# ST_LINK_V3E.net
KiCad netlist of a schematic drawn in Altium Designer
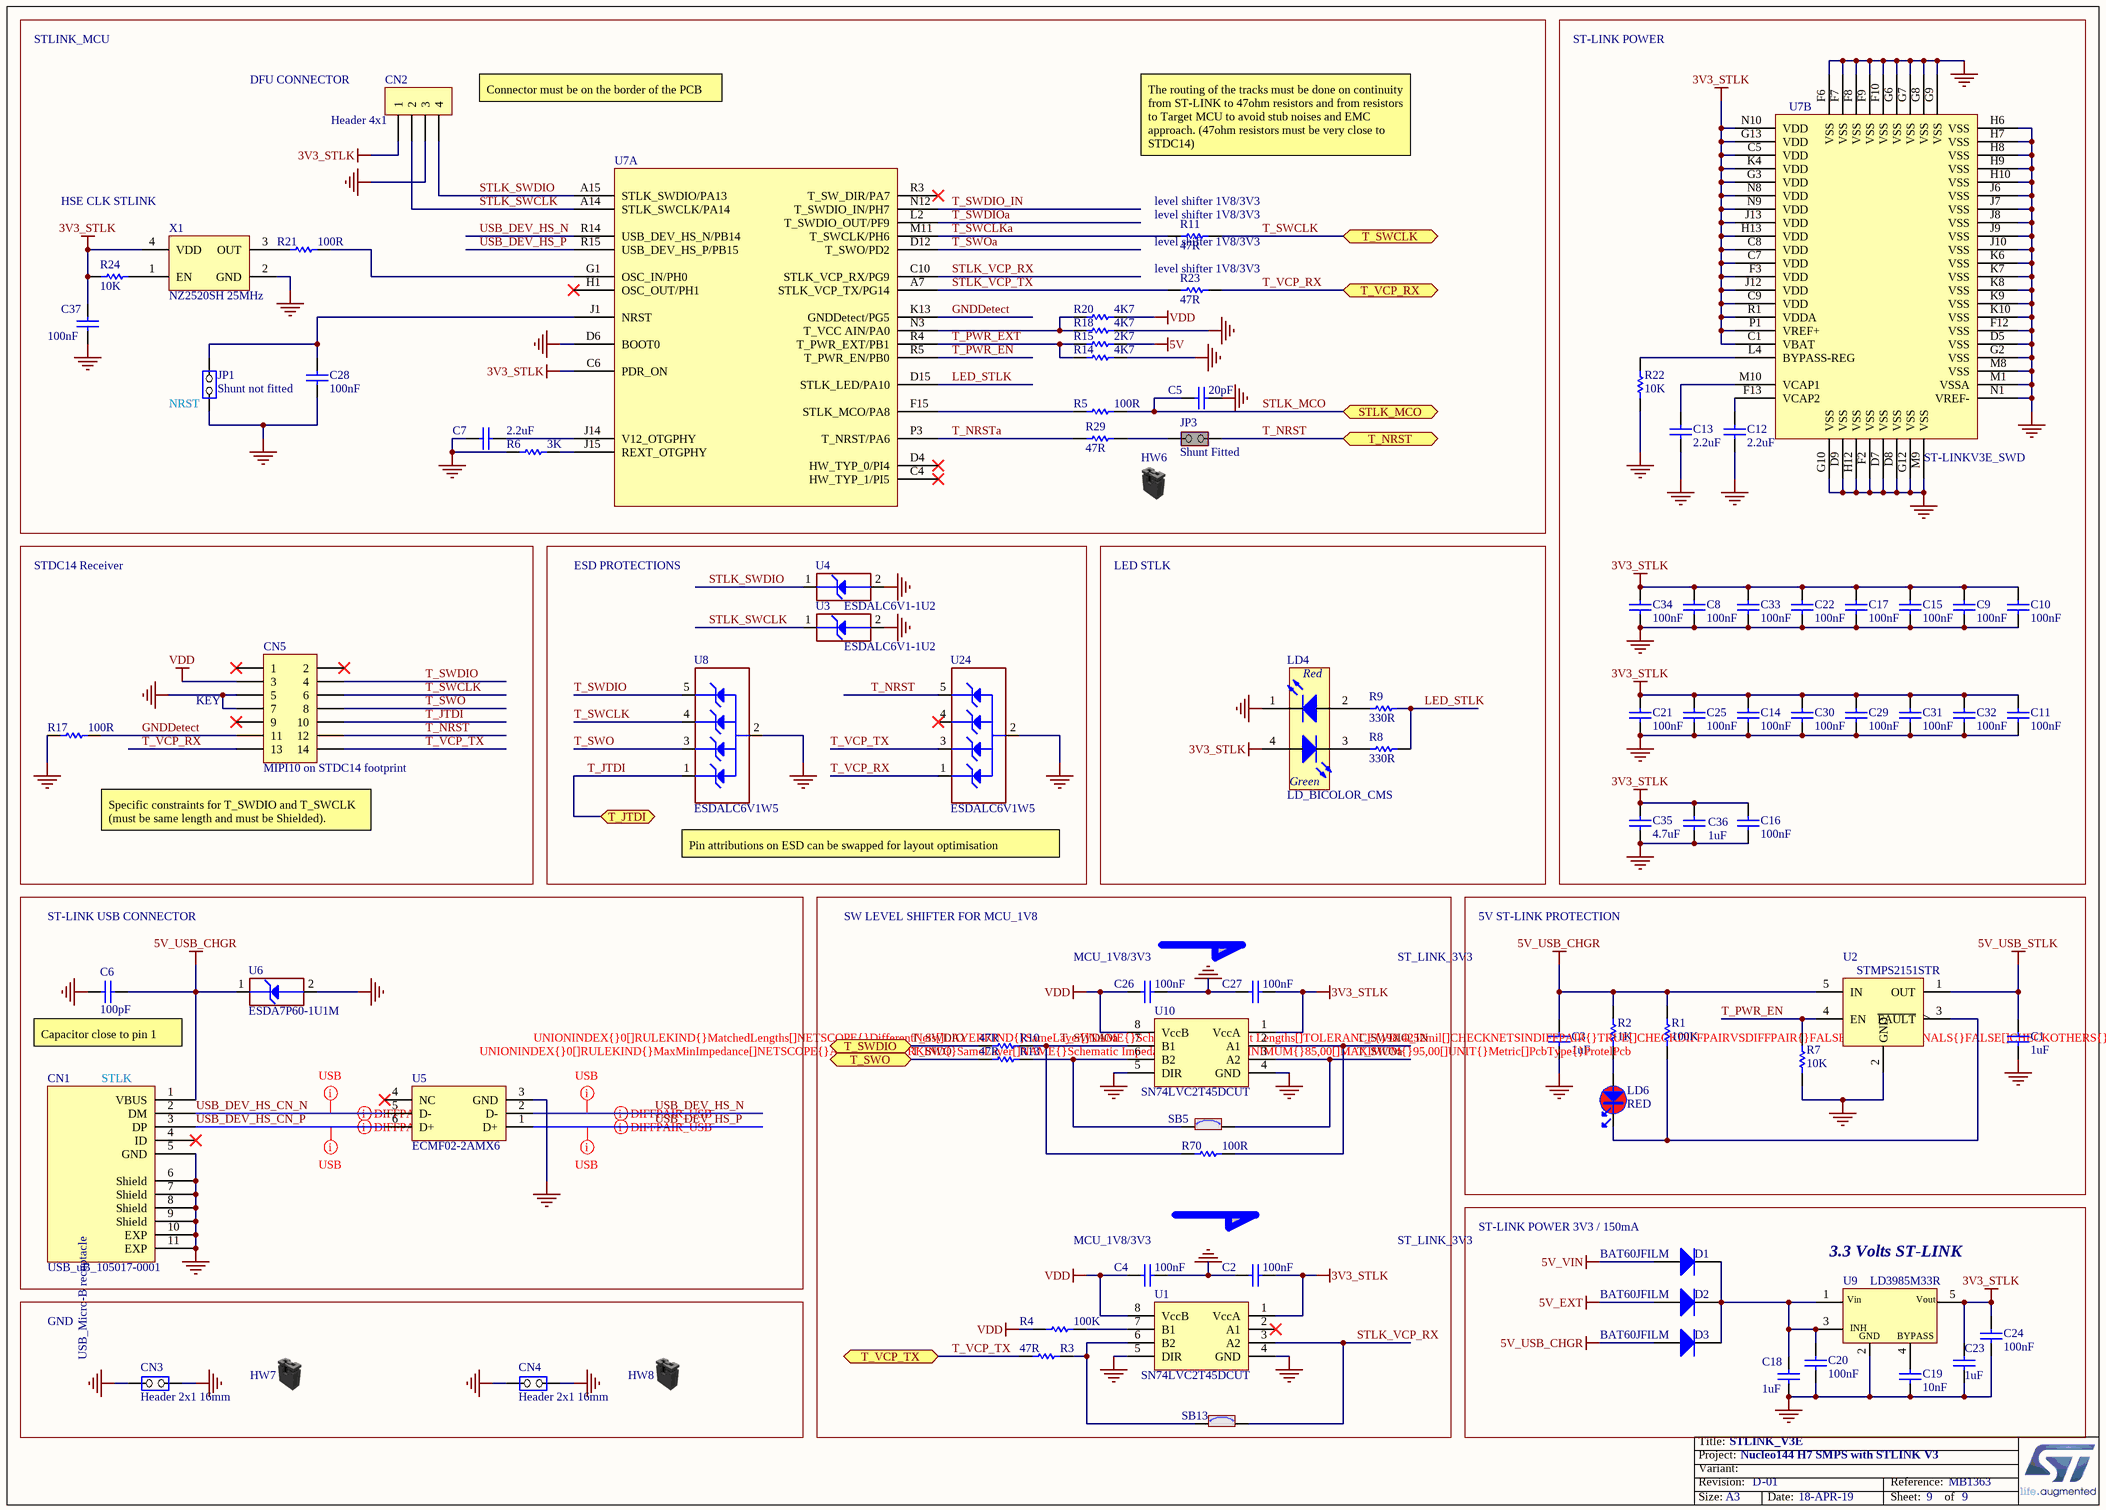
[diagram p0: ST_LINK_V3E.SchDoc]

(export (version "E")
  (design (tool "Eeschema 10.0.6"))
  (components
    (comp (ref "C1")
      (value "1uF")
      (footprint "C0603")
      (description "Capacitor, MLCC, 1uF, 6V3, X5R, 10%, 0603, T=0,8mm")
      (fields
        (field (name "INTERNAL_PART_NUMBER") "MCD-00238")
        (field (name "MANUFACTURER_PART_NUMBER") "CC0603KRX5R5BB105")
        (field (name "PROVIDED_BY") "SUBCO")
      )
      (libsource (lib "MCD_PARTS_database") (part "Capacitor"))
    )
    (comp (ref "C2")
      (value "100nF")
      (footprint "C0603")
      (description "Capacitor, MLCC, 100nF, 16V, X7R, 10%, 0603, T=0,8mm")
      (fields
        (field (name "INTERNAL_PART_NUMBER") "MCD-00211")
        (field (name "MANUFACTURER_PART_NUMBER") "CC0603KRX7R7BB104")
        (field (name "PROVIDED_BY") "SUBCO")
      )
      (libsource (lib "MCD_PARTS_database") (part "Capacitor"))
    )
    (comp (ref "C3")
      (value "1uF")
      (footprint "C0603")
      (description "Capacitor, MLCC, 1uF, 6V3, X5R, 10%, 0603, T=0,8mm")
      (fields
        (field (name "INTERNAL_PART_NUMBER") "MCD-00238")
        (field (name "MANUFACTURER_PART_NUMBER") "CC0603KRX5R5BB105")
        (field (name "PROVIDED_BY") "SUBCO")
      )
      (libsource (lib "MCD_PARTS_database") (part "Capacitor"))
    )
    (comp (ref "C4")
      (value "100nF")
      (footprint "C0603")
      (description "Capacitor, MLCC, 100nF, 16V, X7R, 10%, 0603, T=0,8mm")
      (fields
        (field (name "INTERNAL_PART_NUMBER") "MCD-00211")
        (field (name "MANUFACTURER_PART_NUMBER") "CC0603KRX7R7BB104")
        (field (name "PROVIDED_BY") "SUBCO")
      )
      (libsource (lib "MCD_PARTS_database") (part "Capacitor"))
    )
    (comp (ref "C5")
      (value "20pF")
      (footprint "C0402")
      (description "Capacitor, MLCC, 20pF, 50V, NPO, 5%, 0402, T=0,5mm")
      (fields
        (field (name "INTERNAL_PART_NUMBER") "MCD-00016")
        (field (name "MANUFACTURER_PART_NUMBER") "CC0402JRNPO9BN200")
        (field (name "PROVIDED_BY") "SUBCO")
      )
      (libsource (lib "MCD_PARTS_database") (part "Capacitor"))
    )
    (comp (ref "C6")
      (value "100pF")
      (footprint "C0402")
      (description "Capacitor, MLCC, 100pF, 50V, NPO, 5%, 0402, T=0,5mm")
      (fields
        (field (name "INTERNAL_PART_NUMBER") "MCD-00205")
        (field (name "MANUFACTURER_PART_NUMBER") "CC0402JRNPO9BN101")
        (field (name "PROVIDED_BY") "SUBCO")
      )
      (libsource (lib "MCD_PARTS_database") (part "Capacitor"))
    )
    (comp (ref "C7")
      (value "2.2uF")
      (footprint "C0603")
      (description "Capacitor, MLCC, 2.2uF, 10V, X5R, 10%, 0603, T=0,8mm")
      (fields
        (field (name "INTERNAL_PART_NUMBER") "MCD-00012")
        (field (name "MANUFACTURER_PART_NUMBER") "CC0603KRX5R6BB225")
        (field (name "PROVIDED_BY") "SUBCO")
      )
      (libsource (lib "MCD_PARTS_database") (part "Capacitor"))
    )
    (comp (ref "C8")
      (value "100nF")
      (footprint "C0402")
      (description "Capacitor, MLCC, 100nF, 16V, X7R, 10%, 0402, T=0,5mm")
      (fields
        (field (name "INTERNAL_PART_NUMBER") "MCD-00102")
        (field (name "MANUFACTURER_PART_NUMBER") "CC0402KRX7R7BB104")
        (field (name "PROVIDED_BY") "SUBCO")
      )
      (libsource (lib "MCD_PARTS_database") (part "Capacitor"))
    )
    (comp (ref "C9")
      (value "100nF")
      (footprint "C0402")
      (description "Capacitor, MLCC, 100nF, 16V, X7R, 10%, 0402, T=0,5mm")
      (fields
        (field (name "INTERNAL_PART_NUMBER") "MCD-00102")
        (field (name "MANUFACTURER_PART_NUMBER") "CC0402KRX7R7BB104")
        (field (name "PROVIDED_BY") "SUBCO")
      )
      (libsource (lib "MCD_PARTS_database") (part "Capacitor"))
    )
    (comp (ref "C10")
      (value "100nF")
      (footprint "C0402")
      (description "Capacitor, MLCC, 100nF, 16V, X7R, 10%, 0402, T=0,5mm")
      (fields
        (field (name "INTERNAL_PART_NUMBER") "MCD-00102")
        (field (name "MANUFACTURER_PART_NUMBER") "CC0402KRX7R7BB104")
        (field (name "PROVIDED_BY") "SUBCO")
      )
      (libsource (lib "MCD_PARTS_database") (part "Capacitor"))
    )
    (comp (ref "C11")
      (value "100nF")
      (footprint "C0402")
      (description "Capacitor, MLCC, 100nF, 16V, X7R, 10%, 0402, T=0,5mm")
      (fields
        (field (name "INTERNAL_PART_NUMBER") "MCD-00102")
        (field (name "MANUFACTURER_PART_NUMBER") "CC0402KRX7R7BB104")
        (field (name "PROVIDED_BY") "SUBCO")
      )
      (libsource (lib "MCD_PARTS_database") (part "Capacitor"))
    )
    (comp (ref "C12")
      (value "2.2uF")
      (footprint "C0603")
      (description "Capacitor, MLCC, 2.2uF, 10V, X5R, 10%, 0603, T=0,8mm")
      (fields
        (field (name "INTERNAL_PART_NUMBER") "MCD-00012")
        (field (name "MANUFACTURER_PART_NUMBER") "CC0603KRX5R6BB225")
        (field (name "PROVIDED_BY") "SUBCO")
      )
      (libsource (lib "MCD_PARTS_database") (part "Capacitor"))
    )
    (comp (ref "C13")
      (value "2.2uF")
      (footprint "C0603")
      (description "Capacitor, MLCC, 2.2uF, 10V, X5R, 10%, 0603, T=0,8mm")
      (fields
        (field (name "INTERNAL_PART_NUMBER") "MCD-00012")
        (field (name "MANUFACTURER_PART_NUMBER") "CC0603KRX5R6BB225")
        (field (name "PROVIDED_BY") "SUBCO")
      )
      (libsource (lib "MCD_PARTS_database") (part "Capacitor"))
    )
    (comp (ref "C14")
      (value "100nF")
      (footprint "C0402")
      (description "Capacitor, MLCC, 100nF, 16V, X7R, 10%, 0402, T=0,5mm")
      (fields
        (field (name "INTERNAL_PART_NUMBER") "MCD-00102")
        (field (name "MANUFACTURER_PART_NUMBER") "CC0402KRX7R7BB104")
        (field (name "PROVIDED_BY") "SUBCO")
      )
      (libsource (lib "MCD_PARTS_database") (part "Capacitor"))
    )
    (comp (ref "C15")
      (value "100nF")
      (footprint "C0402")
      (description "Capacitor, MLCC, 100nF, 16V, X7R, 10%, 0402, T=0,5mm")
      (fields
        (field (name "INTERNAL_PART_NUMBER") "MCD-00102")
        (field (name "MANUFACTURER_PART_NUMBER") "CC0402KRX7R7BB104")
        (field (name "PROVIDED_BY") "SUBCO")
      )
      (libsource (lib "MCD_PARTS_database") (part "Capacitor"))
    )
    (comp (ref "C16")
      (value "100nF")
      (footprint "C0402")
      (description "Capacitor, MLCC, 100nF, 16V, X7R, 10%, 0402, T=0,5mm")
      (fields
        (field (name "INTERNAL_PART_NUMBER") "MCD-00102")
        (field (name "MANUFACTURER_PART_NUMBER") "CC0402KRX7R7BB104")
        (field (name "PROVIDED_BY") "SUBCO")
      )
      (libsource (lib "MCD_PARTS_database") (part "Capacitor"))
    )
    (comp (ref "C17")
      (value "100nF")
      (footprint "C0402")
      (description "Capacitor, MLCC, 100nF, 16V, X7R, 10%, 0402, T=0,5mm")
      (fields
        (field (name "INTERNAL_PART_NUMBER") "MCD-00102")
        (field (name "MANUFACTURER_PART_NUMBER") "CC0402KRX7R7BB104")
        (field (name "PROVIDED_BY") "SUBCO")
      )
      (libsource (lib "MCD_PARTS_database") (part "Capacitor"))
    )
    (comp (ref "C18")
      (value "1uF")
      (footprint "C0603")
      (description "Capacitor, MLCC, 1uF, 6V3, X5R, 10%, 0603, T=0,8mm")
      (fields
        (field (name "INTERNAL_PART_NUMBER") "MCD-00238")
        (field (name "MANUFACTURER_PART_NUMBER") "CC0603KRX5R5BB105")
        (field (name "PROVIDED_BY") "SUBCO")
      )
      (libsource (lib "MCD_PARTS_database") (part "Capacitor"))
    )
    (comp (ref "C19")
      (value "10nF")
      (footprint "C0402")
      (description "Capacitor, MLCC, 10nF, 16V, X7R, 10%, 0402, T=0.5mm")
      (fields
        (field (name "INTERNAL_PART_NUMBER") "MCD-00011")
        (field (name "MANUFACTURER_PART_NUMBER") "CC0402KRX7R7BB103")
        (field (name "PROVIDED_BY") "SUBCO")
      )
      (libsource (lib "MCD_PARTS_database") (part "Capacitor"))
    )
    (comp (ref "C20")
      (value "100nF")
      (footprint "C0402")
      (description "Capacitor, MLCC, 100nF, 16V, X7R, 10%, 0402, T=0,5mm")
      (fields
        (field (name "INTERNAL_PART_NUMBER") "MCD-00102")
        (field (name "MANUFACTURER_PART_NUMBER") "CC0402KRX7R7BB104")
        (field (name "PROVIDED_BY") "SUBCO")
      )
      (libsource (lib "MCD_PARTS_database") (part "Capacitor"))
    )
    (comp (ref "C21")
      (value "100nF")
      (footprint "C0402")
      (description "Capacitor, MLCC, 100nF, 16V, X7R, 10%, 0402, T=0,5mm")
      (fields
        (field (name "INTERNAL_PART_NUMBER") "MCD-00102")
        (field (name "MANUFACTURER_PART_NUMBER") "CC0402KRX7R7BB104")
        (field (name "PROVIDED_BY") "SUBCO")
      )
      (libsource (lib "MCD_PARTS_database") (part "Capacitor"))
    )
    (comp (ref "C22")
      (value "100nF")
      (footprint "C0402")
      (description "Capacitor, MLCC, 100nF, 16V, X7R, 10%, 0402, T=0,5mm")
      (fields
        (field (name "INTERNAL_PART_NUMBER") "MCD-00102")
        (field (name "MANUFACTURER_PART_NUMBER") "CC0402KRX7R7BB104")
        (field (name "PROVIDED_BY") "SUBCO")
      )
      (libsource (lib "MCD_PARTS_database") (part "Capacitor"))
    )
    (comp (ref "C23")
      (value "1uF")
      (footprint "C0603")
      (description "Capacitor, MLCC, 1uF, 16V, X5R, 10%, 0603, T=0,8mm")
      (fields
        (field (name "INTERNAL_PART_NUMBER") "MCD-00010")
        (field (name "MANUFACTURER_PART_NUMBER") "CC0603KRX5R7BB105")
        (field (name "PROVIDED_BY") "SUBCO")
      )
      (libsource (lib "MCD_PARTS_database") (part "Capacitor"))
    )
    (comp (ref "C24")
      (value "100nF")
      (footprint "C0402")
      (description "Capacitor, MLCC, 100nF, 16V, X7R, 10%, 0402, T=0,5mm")
      (fields
        (field (name "INTERNAL_PART_NUMBER") "MCD-00102")
        (field (name "MANUFACTURER_PART_NUMBER") "CC0402KRX7R7BB104")
        (field (name "PROVIDED_BY") "SUBCO")
      )
      (libsource (lib "MCD_PARTS_database") (part "Capacitor"))
    )
    (comp (ref "C25")
      (value "100nF")
      (footprint "C0402")
      (description "Capacitor, MLCC, 100nF, 16V, X7R, 10%, 0402, T=0,5mm")
      (fields
        (field (name "INTERNAL_PART_NUMBER") "MCD-00102")
        (field (name "MANUFACTURER_PART_NUMBER") "CC0402KRX7R7BB104")
        (field (name "PROVIDED_BY") "SUBCO")
      )
      (libsource (lib "MCD_PARTS_database") (part "Capacitor"))
    )
    (comp (ref "C26")
      (value "100nF")
      (footprint "C0603")
      (description "Capacitor, MLCC, 100nF, 6V3, X5R, 10%, 0603, T=0,8mm")
      (fields
        (field (name "INTERNAL_PART_NUMBER") "MCD-00237")
        (field (name "MANUFACTURER_PART_NUMBER") "CC0603KRX5R5BB104")
        (field (name "PROVIDED_BY") "SUBCO")
      )
      (libsource (lib "MCD_PARTS_database") (part "Capacitor"))
    )
    (comp (ref "C27")
      (value "100nF")
      (footprint "C0603")
      (description "Capacitor, MLCC, 100nF, 6V3, X5R, 10%, 0603, T=0,8mm")
      (fields
        (field (name "INTERNAL_PART_NUMBER") "MCD-00237")
        (field (name "MANUFACTURER_PART_NUMBER") "CC0603KRX5R5BB104")
        (field (name "PROVIDED_BY") "SUBCO")
      )
      (libsource (lib "MCD_PARTS_database") (part "Capacitor"))
    )
    (comp (ref "C28")
      (value "100nF")
      (footprint "C0402")
      (description "Capacitor, MLCC, 100nF, 16V, X7R, 10%, 0402, T=0,5mm")
      (fields
        (field (name "INTERNAL_PART_NUMBER") "MCD-00102")
        (field (name "MANUFACTURER_PART_NUMBER") "CC0402KRX7R7BB104")
        (field (name "PROVIDED_BY") "SUBCO")
      )
      (libsource (lib "MCD_PARTS_database") (part "Capacitor"))
    )
    (comp (ref "C29")
      (value "100nF")
      (footprint "C0402")
      (description "Capacitor, MLCC, 100nF, 16V, X7R, 10%, 0402, T=0,5mm")
      (fields
        (field (name "INTERNAL_PART_NUMBER") "MCD-00102")
        (field (name "MANUFACTURER_PART_NUMBER") "CC0402KRX7R7BB104")
        (field (name "PROVIDED_BY") "SUBCO")
      )
      (libsource (lib "MCD_PARTS_database") (part "Capacitor"))
    )
    (comp (ref "C30")
      (value "100nF")
      (footprint "C0402")
      (description "Capacitor, MLCC, 100nF, 16V, X7R, 10%, 0402, T=0,5mm")
      (fields
        (field (name "INTERNAL_PART_NUMBER") "MCD-00102")
        (field (name "MANUFACTURER_PART_NUMBER") "CC0402KRX7R7BB104")
        (field (name "PROVIDED_BY") "SUBCO")
      )
      (libsource (lib "MCD_PARTS_database") (part "Capacitor"))
    )
    (comp (ref "C31")
      (value "100nF")
      (footprint "C0402")
      (description "Capacitor, MLCC, 100nF, 16V, X7R, 10%, 0402, T=0,5mm")
      (fields
        (field (name "INTERNAL_PART_NUMBER") "MCD-00102")
        (field (name "MANUFACTURER_PART_NUMBER") "CC0402KRX7R7BB104")
        (field (name "PROVIDED_BY") "SUBCO")
      )
      (libsource (lib "MCD_PARTS_database") (part "Capacitor"))
    )
    (comp (ref "C32")
      (value "100nF")
      (footprint "C0402")
      (description "Capacitor, MLCC, 100nF, 16V, X7R, 10%, 0402, T=0,5mm")
      (fields
        (field (name "INTERNAL_PART_NUMBER") "MCD-00102")
        (field (name "MANUFACTURER_PART_NUMBER") "CC0402KRX7R7BB104")
        (field (name "PROVIDED_BY") "SUBCO")
      )
      (libsource (lib "MCD_PARTS_database") (part "Capacitor"))
    )
    (comp (ref "C33")
      (value "100nF")
      (footprint "C0402")
      (description "Capacitor, MLCC, 100nF, 16V, X7R, 10%, 0402, T=0,5mm")
      (fields
        (field (name "INTERNAL_PART_NUMBER") "MCD-00102")
        (field (name "MANUFACTURER_PART_NUMBER") "CC0402KRX7R7BB104")
        (field (name "PROVIDED_BY") "SUBCO")
      )
      (libsource (lib "MCD_PARTS_database") (part "Capacitor"))
    )
    (comp (ref "C34")
      (value "100nF")
      (footprint "C0402")
      (description "Capacitor, MLCC, 100nF, 16V, X7R, 10%, 0402, T=0,5mm")
      (fields
        (field (name "INTERNAL_PART_NUMBER") "MCD-00102")
        (field (name "MANUFACTURER_PART_NUMBER") "CC0402KRX7R7BB104")
        (field (name "PROVIDED_BY") "SUBCO")
      )
      (libsource (lib "MCD_PARTS_database") (part "Capacitor"))
    )
    (comp (ref "C35")
      (value "4.7uF")
      (footprint "C0603")
      (description "Capacitor, MLCC, 4.7uF, 16V, X5R, 10%, 0603, T=0.8mm")
      (fields
        (field (name "INTERNAL_PART_NUMBER") "MCD-00009")
        (field (name "MANUFACTURER_PART_NUMBER") "CC0603KRX5R7BB475")
        (field (name "PROVIDED_BY") "SUBCO")
      )
      (libsource (lib "MCD_PARTS_database") (part "Capacitor"))
    )
    (comp (ref "C36")
      (value "1uF")
      (footprint "C0603")
      (description "Capacitor, MLCC, 1uF, 16V, X5R, 10%, 0603, T=0,8mm")
      (fields
        (field (name "INTERNAL_PART_NUMBER") "MCD-00010")
        (field (name "MANUFACTURER_PART_NUMBER") "CC0603KRX5R7BB105")
        (field (name "PROVIDED_BY") "SUBCO")
      )
      (libsource (lib "MCD_PARTS_database") (part "Capacitor"))
    )
    (comp (ref "C37")
      (value "100nF")
      (footprint "C0402")
      (description "Capacitor, MLCC, 100nF, 16V, X7R, 10%, 0402, T=0,5mm")
      (fields
        (field (name "INTERNAL_PART_NUMBER") "MCD-00102")
        (field (name "MANUFACTURER_PART_NUMBER") "CC0402KRX7R7BB104")
        (field (name "PROVIDED_BY") "SUBCO")
      )
      (libsource (lib "MCD_PARTS_database") (part "Capacitor"))
    )
    (comp (ref "CN1")
      (value "USB_uB_105017-0001")
      (footprint "CON_USBMICROB_MOLEX_105017-0001_H2P90")
      (description "USB-MICRO-B, 0.65mm, RA, SMT, Bottom Mount,")
      (fields
        (field (name "INTERNAL_PART_NUMBER") "MCD-00028")
        (field (name "MANUFACTURER_PART_NUMBER") "1050170001")
        (field (name "PROVIDED_BY") "SUBCO")
      )
      (libsource (lib "MCD_PARTS_database") (part "USB_uB_105017.0001"))
    )
    (comp (ref "CN2")
      (value "Header 4x1")
      (footprint "CON_SAMTEC_TSW-104-07-G-S")
      (description "Header, 4x1, 2,54mm, VR, TH, Height 5.84mm/2.54mm")
      (fields
        (field (name "INTERNAL_PART_NUMBER") "MCD-00029")
        (field (name "MANUFACTURER_PART_NUMBER") "TSW-104-07-x-S")
        (field (name "PROVIDED_BY") "SUBCO")
      )
      (libsource (lib "MCD_PARTS_database") (part "Header 4x1"))
    )
    (comp (ref "CN3")
      (value "Header 2x1 16mm")
      (footprint "CON_SAMTEC_TSW-102-09-X-S")
      (description "Header, 2x1, 2,54mm, VR, TH, Height 5.84mm/10.16mm")
      (fields
        (field (name "INTERNAL_PART_NUMBER") "MCD-00214")
        (field (name "MANUFACTURER_PART_NUMBER") "TSW-102-09-x-S")
        (field (name "PROVIDED_BY") "SUBCO")
      )
      (libsource (lib "MCD_PARTS_database") (part "Jumper_Header 2x1"))
    )
    (comp (ref "CN4")
      (value "Header 2x1 16mm")
      (footprint "CON_SAMTEC_TSW-102-09-X-S")
      (description "Header, 2x1, 2,54mm, VR, TH, Height 5.84mm/10.16mm")
      (fields
        (field (name "INTERNAL_PART_NUMBER") "MCD-00214")
        (field (name "MANUFACTURER_PART_NUMBER") "TSW-102-09-x-S")
        (field (name "PROVIDED_BY") "SUBCO")
      )
      (libsource (lib "MCD_PARTS_database") (part "Jumper_Header 2x1"))
    )
    (comp (ref "CN5")
      (value "MIPI10 on STDC14 footprint")
      (footprint "CON_STDC14_Receiver_MEDIUM_WITH_MIPI10_3D")
      (fields
        (field (name "INTERNAL_PART_NUMBER") "MCD-01226")
        (field (name "MANUFACTURER_PART_NUMBER") "FTSH-105-01-L-DV-K")
        (field (name "MANUFACTURER") "SAMTEC")
        (field (name "PROVIDED_BY") "SUBCO")
      )
      (libsource (lib "MCD_PARTS_database") (part "Header 7x2"))
    )
    (comp (ref "D1")
      (value "BAT60JFILM")
      (footprint "DIO_SOD323")
      (fields
        (field (name "INTERNAL_PART_NUMBER") "MCD-00034")
        (field (name "MANUFACTURER") "STMICROELECTRONICS")
        (field (name "BMS_PART_NUMBER") "9151097")
        (field (name "PROVIDED_BY") "SUBCO with ST control")
      )
      (libsource (lib "MCD_PARTS_database") (part "BAT60JFILM"))
    )
    (comp (ref "D2")
      (value "BAT60JFILM")
      (footprint "DIO_SOD323")
      (fields
        (field (name "INTERNAL_PART_NUMBER") "MCD-00034")
        (field (name "MANUFACTURER") "STMICROELECTRONICS")
        (field (name "BMS_PART_NUMBER") "9151097")
        (field (name "PROVIDED_BY") "SUBCO with ST control")
      )
      (libsource (lib "MCD_PARTS_database") (part "BAT60JFILM"))
    )
    (comp (ref "D3")
      (value "BAT60JFILM")
      (footprint "DIO_SOD323")
      (fields
        (field (name "INTERNAL_PART_NUMBER") "MCD-00034")
        (field (name "MANUFACTURER") "STMICROELECTRONICS")
        (field (name "BMS_PART_NUMBER") "9151097")
        (field (name "PROVIDED_BY") "SUBCO with ST control")
      )
      (libsource (lib "MCD_PARTS_database") (part "BAT60JFILM"))
    )
    (comp (ref "HW6")
      (value "Shunt Black 2.54mm")
      (description "SHUNT 2.54mm BLACK")
      (fields
        (field (name "INTERNAL_PART_NUMBER") "MCD-00043")
        (field (name "MANUFACTURER_PART_NUMBER") "SNT-100-BK-G")
        (field (name "PROVIDED_BY") "SUBCO")
      )
      (libsource (lib "MCD_PARTS_database") (part "Shunt Black 2.54mm"))
    )
    (comp (ref "HW7")
      (value "Shunt Black 2.54mm")
      (description "SHUNT 2.54mm BLACK")
      (fields
        (field (name "INTERNAL_PART_NUMBER") "MCD-00043")
        (field (name "MANUFACTURER_PART_NUMBER") "SNT-100-BK-G")
        (field (name "PROVIDED_BY") "SUBCO")
      )
      (libsource (lib "MCD_PARTS_database") (part "Shunt Black 2.54mm"))
    )
    (comp (ref "HW8")
      (value "Shunt Black 2.54mm")
      (description "SHUNT 2.54mm BLACK")
      (fields
        (field (name "INTERNAL_PART_NUMBER") "MCD-00043")
        (field (name "MANUFACTURER_PART_NUMBER") "SNT-100-BK-G")
        (field (name "PROVIDED_BY") "SUBCO")
      )
      (libsource (lib "MCD_PARTS_database") (part "Shunt Black 2.54mm"))
    )
    (comp (ref "JP1")
      (value "Shunt not fitted")
      (footprint "CON_SAMTEC_TSW-102-07-G-S")
      (description "Header, 2x1, 2,54mm, VR, TH, Height 5.84mm/2.54mm")
      (fields
        (field (name "INTERNAL_PART_NUMBER") "MCD-00045")
        (field (name "MANUFACTURER_PART_NUMBER") "TSW-102-07-x-S")
        (field (name "PROVIDED_BY") "SUBCO")
      )
      (libsource (lib "MCD_PARTS_database") (part "Jumper_Header 2x1"))
    )
    (comp (ref "JP3")
      (value "Shunt Fitted")
      (footprint "CON_SAMTEC_TSW-102-07-G-S")
      (description "Header, 2x1, 2,54mm, VR, TH, Height 5.84mm/2.54mm - Shunt Fitted by default")
      (fields
        (field (name "INTERNAL_PART_NUMBER") "MCD-00683")
        (field (name "MANUFACTURER_PART_NUMBER") "TSW-102-07-x-S")
        (field (name "PROVIDED_BY") "SUBCO")
      )
      (libsource (lib "MCD_PARTS_database") (part "Jumper_Header 2x1 Fitted"))
    )
    (comp (ref "LD4")
      (value "LD_BICOLOR_CMS")
      (footprint "LED_BI-GR_HSMF-A201-A00J1")
      (description "LED Bicolor")
      (fields
        (field (name "INTERNAL_PART_NUMBER") "MCD-00051")
        (field (name "MANUFACTURER_PART_NUMBER") "HSMF-A201-A00J1")
        (field (name "PROVIDED_BY") "SUBCO")
      )
      (libsource (lib "MCD_PARTS_database") (part "LD_BICOLOR_CMS"))
    )
    (comp (ref "LD6")
      (value "RED")
      (footprint "LED_0603_RED")
      (description "LED, Red, 0603")
      (fields
        (field (name "INTERNAL_PART_NUMBER") "MCD-00049")
        (field (name "MANUFACTURER_PART_NUMBER") "19-213-R6C-AP1Q2B/3T")
        (field (name "PROVIDED_BY") "SUBCO")
      )
      (libsource (lib "MCD_PARTS_database") (part "LED_red"))
    )
    (comp (ref "R1")
      (value "100K")
      (footprint "R0603")
      (description "Resistor,100K,0603,1%,1/10W")
      (fields
        (field (name "INTERNAL_PART_NUMBER") "MCD-00223")
        (field (name "MANUFACTURER_PART_NUMBER") "RC0603FR-07100KL")
        (field (name "PROVIDED_BY") "SUBCO")
      )
      (libsource (lib "MCD_PARTS_database") (part "Resistor"))
    )
    (comp (ref "R2")
      (value "1K")
      (footprint "R0603")
      (description "Resistor,1K,0603,1%,1/10W")
      (fields
        (field (name "INTERNAL_PART_NUMBER") "MCD-00070")
        (field (name "MANUFACTURER_PART_NUMBER") "RC0603FR-071KL")
        (field (name "PROVIDED_BY") "SUBCO")
      )
      (libsource (lib "MCD_PARTS_database") (part "Resistor"))
    )
    (comp (ref "R3")
      (value "47R")
      (footprint "R0402")
      (description "Resistor,47R,0402,1%,1/16W")
      (fields
        (field (name "INTERNAL_PART_NUMBER") "MCD-00481")
        (field (name "MANUFACTURER_PART_NUMBER") "RC0402FR-0747RL")
        (field (name "PROVIDED_BY") "SUBCO")
      )
      (libsource (lib "MCD_PARTS_database") (part "Resistor"))
    )
    (comp (ref "R4")
      (value "100K")
      (footprint "R0603")
      (description "Resistor,100K,0603,1%,1/10W")
      (fields
        (field (name "INTERNAL_PART_NUMBER") "MCD-00223")
        (field (name "MANUFACTURER_PART_NUMBER") "RC0603FR-07100KL")
        (field (name "PROVIDED_BY") "SUBCO")
      )
      (libsource (lib "MCD_PARTS_database") (part "Resistor"))
    )
    (comp (ref "R5")
      (value "100R")
      (footprint "R0402")
      (description "Resistor,100R,0402,1%,1/16W")
      (fields
        (field (name "INTERNAL_PART_NUMBER") "MCD-00119")
        (field (name "MANUFACTURER_PART_NUMBER") "RC0402FR-07100RL")
        (field (name "PROVIDED_BY") "SUBCO")
      )
      (libsource (lib "MCD_PARTS_database") (part "Resistor"))
    )
    (comp (ref "R6")
      (value "3K")
      (footprint "R0402")
      (description "Resistor,3K,0402,1%,1/16W")
      (fields
        (field (name "INTERNAL_PART_NUMBER") "MCD-00185")
        (field (name "MANUFACTURER_PART_NUMBER") "RC0402FR-073KL")
        (field (name "PROVIDED_BY") "SUBCO")
      )
      (libsource (lib "MCD_PARTS_database") (part "Resistor"))
    )
    (comp (ref "R7")
      (value "10K")
      (footprint "R0603")
      (description "Resistor,10K,0603,1%,1/10W")
      (fields
        (field (name "INTERNAL_PART_NUMBER") "MCD-00220")
        (field (name "MANUFACTURER_PART_NUMBER") "RC0603FR-0710KL")
        (field (name "PROVIDED_BY") "SUBCO")
      )
      (libsource (lib "MCD_PARTS_database") (part "Resistor"))
    )
    (comp (ref "R8")
      (value "330R")
      (footprint "R0603")
      (description "Resistor,330R,0603,1%,1/10W")
      (fields
        (field (name "INTERNAL_PART_NUMBER") "MCD-00197")
        (field (name "MANUFACTURER_PART_NUMBER") "RC0603FR-07330RL")
        (field (name "PROVIDED_BY") "SUBCO")
      )
      (libsource (lib "MCD_PARTS_database") (part "Resistor"))
    )
    (comp (ref "R9")
      (value "330R")
      (footprint "R0603")
      (description "Resistor,330R,0603,1%,1/10W")
      (fields
        (field (name "INTERNAL_PART_NUMBER") "MCD-00197")
        (field (name "MANUFACTURER_PART_NUMBER") "RC0603FR-07330RL")
        (field (name "PROVIDED_BY") "SUBCO")
      )
      (libsource (lib "MCD_PARTS_database") (part "Resistor"))
    )
    (comp (ref "R10")
      (value "47R")
      (footprint "R0402")
      (description "Resistor,47R,0402,1%,1/16W")
      (fields
        (field (name "INTERNAL_PART_NUMBER") "MCD-00481")
        (field (name "MANUFACTURER_PART_NUMBER") "RC0402FR-0747RL")
        (field (name "PROVIDED_BY") "SUBCO")
      )
      (libsource (lib "MCD_PARTS_database") (part "Resistor"))
    )
    (comp (ref "R11")
      (value "47R")
      (footprint "R0402")
      (description "Resistor,47R,0402,1%,1/16W")
      (fields
        (field (name "INTERNAL_PART_NUMBER") "MCD-00481")
        (field (name "MANUFACTURER_PART_NUMBER") "RC0402FR-0747RL")
        (field (name "PROVIDED_BY") "SUBCO")
      )
      (libsource (lib "MCD_PARTS_database") (part "Resistor"))
    )
    (comp (ref "R13")
      (value "47R")
      (footprint "R0402")
      (description "Resistor,47R,0402,1%,1/16W")
      (fields
        (field (name "INTERNAL_PART_NUMBER") "MCD-00481")
        (field (name "MANUFACTURER_PART_NUMBER") "RC0402FR-0747RL")
        (field (name "PROVIDED_BY") "SUBCO")
      )
      (libsource (lib "MCD_PARTS_database") (part "Resistor"))
    )
    (comp (ref "R14")
      (value "4K7")
      (footprint "R0402")
      (description "Resistor,4K7,0402,1%,1/16W")
      (fields
        (field (name "INTERNAL_PART_NUMBER") "MCD-00065")
        (field (name "MANUFACTURER_PART_NUMBER") "RC0402FR-074K7L")
        (field (name "PROVIDED_BY") "SUBCO")
      )
      (libsource (lib "MCD_PARTS_database") (part "Resistor"))
    )
    (comp (ref "R15")
      (value "2K7")
      (footprint "R0402")
      (description "Resistor,2K7,0402,1%,1/16W")
      (fields
        (field (name "INTERNAL_PART_NUMBER") "MCD-00055")
        (field (name "MANUFACTURER_PART_NUMBER") "RC0402FR-072K7L")
        (field (name "PROVIDED_BY") "SUBCO")
      )
      (libsource (lib "MCD_PARTS_database") (part "Resistor"))
    )
    (comp (ref "R17")
      (value "100R")
      (footprint "R0402")
      (description "Resistor,100R,0402,1%,1/16W")
      (fields
        (field (name "INTERNAL_PART_NUMBER") "MCD-00119")
        (field (name "MANUFACTURER_PART_NUMBER") "RC0402FR-07100RL")
        (field (name "PROVIDED_BY") "SUBCO")
      )
      (libsource (lib "MCD_PARTS_database") (part "Resistor"))
    )
    (comp (ref "R18")
      (value "4K7")
      (footprint "R0402")
      (description "Resistor,4K7,0402,1%,1/16W")
      (fields
        (field (name "INTERNAL_PART_NUMBER") "MCD-00065")
        (field (name "MANUFACTURER_PART_NUMBER") "RC0402FR-074K7L")
        (field (name "PROVIDED_BY") "SUBCO")
      )
      (libsource (lib "MCD_PARTS_database") (part "Resistor"))
    )
    (comp (ref "R20")
      (value "4K7")
      (footprint "R0402")
      (description "Resistor,4K7,0402,1%,1/16W")
      (fields
        (field (name "INTERNAL_PART_NUMBER") "MCD-00065")
        (field (name "MANUFACTURER_PART_NUMBER") "RC0402FR-074K7L")
        (field (name "PROVIDED_BY") "SUBCO")
      )
      (libsource (lib "MCD_PARTS_database") (part "Resistor"))
    )
    (comp (ref "R21")
      (value "100R")
      (footprint "R0402")
      (description "Resistor,100R,0402,1%,1/16W")
      (fields
        (field (name "INTERNAL_PART_NUMBER") "MCD-00119")
        (field (name "MANUFACTURER_PART_NUMBER") "RC0402FR-07100RL")
        (field (name "PROVIDED_BY") "SUBCO")
      )
      (libsource (lib "MCD_PARTS_database") (part "Resistor"))
    )
    (comp (ref "R22")
      (value "10K")
      (footprint "R0402")
      (description "Resistor,10K,0402,1%,1/16W")
      (fields
        (field (name "INTERNAL_PART_NUMBER") "MCD-00053")
        (field (name "MANUFACTURER_PART_NUMBER") "RC0402FR-0710KL")
        (field (name "PROVIDED_BY") "SUBCO")
      )
      (libsource (lib "MCD_PARTS_database") (part "Resistor"))
    )
    (comp (ref "R23")
      (value "47R")
      (footprint "R0402")
      (description "Resistor,47R,0402,1%,1/16W")
      (fields
        (field (name "INTERNAL_PART_NUMBER") "MCD-00481")
        (field (name "MANUFACTURER_PART_NUMBER") "RC0402FR-0747RL")
        (field (name "PROVIDED_BY") "SUBCO")
      )
      (libsource (lib "MCD_PARTS_database") (part "Resistor"))
    )
    (comp (ref "R24")
      (value "10K")
      (footprint "R0402")
      (description "Resistor,10K,0402,1%,1/16W")
      (fields
        (field (name "INTERNAL_PART_NUMBER") "MCD-00053")
        (field (name "MANUFACTURER_PART_NUMBER") "RC0402FR-0710KL")
        (field (name "PROVIDED_BY") "SUBCO")
      )
      (libsource (lib "MCD_PARTS_database") (part "Resistor"))
    )
    (comp (ref "R29")
      (value "47R")
      (footprint "R0402")
      (description "Resistor,47R,0402,1%,1/16W")
      (fields
        (field (name "INTERNAL_PART_NUMBER") "MCD-00481")
        (field (name "MANUFACTURER_PART_NUMBER") "RC0402FR-0747RL")
        (field (name "PROVIDED_BY") "SUBCO")
      )
      (libsource (lib "MCD_PARTS_database") (part "Resistor"))
    )
    (comp (ref "R70")
      (value "100R")
      (footprint "R0402")
      (description "Resistor,100R,0402,1%,1/16W")
      (fields
        (field (name "INTERNAL_PART_NUMBER") "MCD-00119")
        (field (name "MANUFACTURER_PART_NUMBER") "RC0402FR-07100RL")
        (field (name "PROVIDED_BY") "SUBCO")
      )
      (libsource (lib "MCD_PARTS_database") (part "Resistor"))
    )
    (comp (ref "SB5")
      (value "SB_ON")
      (footprint "SOLDER-BRIDGE_R0603-0R")
      (description "Solder Bridge ON")
      (fields
        (field (name "INTERNAL_PART_NUMBER") "MCD-00071")
        (field (name "MANUFACTURER_PART_NUMBER") "RC0603JR-070RL")
        (field (name "PROVIDED_BY") "SUBCO")
      )
      (libsource (lib "MCD_PARTS_database") (part "SB_ON"))
    )
    (comp (ref "SB13")
      (value "SB_ON")
      (footprint "SOLDER-BRIDGE_R0603-0R")
      (description "Solder Bridge ON")
      (fields
        (field (name "INTERNAL_PART_NUMBER") "MCD-00071")
        (field (name "MANUFACTURER_PART_NUMBER") "RC0603JR-070RL")
        (field (name "PROVIDED_BY") "SUBCO")
      )
      (libsource (lib "MCD_PARTS_database") (part "SB_ON"))
    )
    (comp (ref "U1")
      (value "SN74LVC2T45DCUT")
      (footprint "ICC_VSSOP8_DCU_R-PDSO-G8_2X2P30_P050")
      (description "Dual bit dual supply bus transceiver")
      (fields
        (field (name "INTERNAL_PART_NUMBER") "MCD-00264")
        (field (name "MANUFACTURER") "TEXAS INSTRUMENTS")
        (field (name "PROVIDED_BY") "SUBCO")
      )
      (libsource (lib "MCD_PARTS_database") (part "SN74LVC2T45DCUT"))
    )
    (comp (ref "U2")
      (value "STMPS2151STR")
      (footprint "MOS_SOT23-5L")
      (description "500mA, Enhanced single channel power switches with active high enable pin")
      (fields
        (field (name "INTERNAL_PART_NUMBER") "MCD-00159")
        (field (name "MANUFACTURER") "STMICROELECTRONICS")
        (field (name "PROVIDED_BY") "SUBCO with ST control")
      )
      (libsource (lib "MCD_PARTS_database") (part "STMPS2151STR"))
    )
    (comp (ref "U3")
      (value "ESDALC6V1-1U2")
      (footprint "ESD_ST0201")
      (description "ESD protection 6V1")
      (fields
        (field (name "INTERNAL_PART_NUMBER") "MCD-00170")
        (field (name "MANUFACTURER") "STMICROELECTRONICS")
        (field (name "PROVIDED_BY") "SUBCO with ST control")
      )
      (libsource (lib "MCD_PARTS_database") (part "ESD-TRANSIL"))
    )
    (comp (ref "U4")
      (value "ESDALC6V1-1U2")
      (footprint "ESD_ST0201")
      (description "ESD protection 6V1")
      (fields
        (field (name "INTERNAL_PART_NUMBER") "MCD-00170")
        (field (name "MANUFACTURER") "STMICROELECTRONICS")
        (field (name "PROVIDED_BY") "SUBCO with ST control")
      )
      (libsource (lib "MCD_PARTS_database") (part "ESD-TRANSIL"))
    )
    (comp (ref "U5")
      (value "ECMF02-2AMX6")
      (footprint "ESD_QFN-6L_1P7X1P5_P050")
      (description "Common mode filter with ESD protection for USB 2.0 interface")
      (fields
        (field (name "INTERNAL_PART_NUMBER") "MCD-00649")
        (field (name "MANUFACTURER") "STMICROELECTRONICS")
        (field (name "PROVIDED_BY") "SUBCO with ST control")
      )
      (libsource (lib "MCD_PARTS_database") (part "ECMF02-2AMX6"))
    )
    (comp (ref "U6")
      (value "ESDA7P60-1U1M")
      (footprint "ESD_QFN2_1P6X1_P125")
      (description "High power transient voltage suppressor, 7V breakdown")
      (fields
        (field (name "INTERNAL_PART_NUMBER") "MCD-00251")
        (field (name "MANUFACTURER") "STMICROELECTRONICS")
        (field (name "PROVIDED_BY") "SUBCO with ST control")
      )
      (libsource (lib "MCD_PARTS_database") (part "ESD-TRANSIL"))
    )
    (comp (ref "U7")
      (value "ST-LINKV3E_SWD")
      (footprint "ICC_UFBGA201_176+25_10X10_P065")
      (description "STM32F723IEK  (STM32F7) BGA176")
      (fields
        (field (name "INTERNAL_PART_NUMBER") "MCD-00596")
        (field (name "MANUFACTURER_PART_NUMBER") "STM32F723IEK6")
        (field (name "PROVIDED_BY") "SUBCO with ST control")
      )
      (libsource (lib "MCD_PARTS_database") (part "ST-LINKV3E_SWD"))
    )
    (comp (ref "U8")
      (value "ESDALC6V1W5")
      (footprint "ESD_SOT323-5L")
      (description "Dual Transil array for ESD protection")
      (fields
        (field (name "INTERNAL_PART_NUMBER") "MCD-00136")
        (field (name "MANUFACTURER") "STMICROELECTRONICS")
        (field (name "PROVIDED_BY") "SUBCO with ST control")
      )
      (libsource (lib "MCD_PARTS_database") (part "ESDALC6V1W5"))
    )
    (comp (ref "U9")
      (value "LD3985M33R")
      (footprint "REG_SOT23-5L")
      (description "Ultra low drop-low noise BiCMOS voltage, regulators low ESR capacitors compatible")
      (fields
        (field (name "INTERNAL_PART_NUMBER") "MCD-00086")
        (field (name "MANUFACTURER") "STMICROELECTRONICS")
        (field (name "PROVIDED_BY") "SUBCO with ST control")
      )
      (libsource (lib "MCD_PARTS_database") (part "LD3985M33R"))
    )
    (comp (ref "U10")
      (value "SN74LVC2T45DCUT")
      (footprint "ICC_VSSOP8_DCU_R-PDSO-G8_2X2P30_P050")
      (description "Dual bit dual supply bus transceiver")
      (fields
        (field (name "INTERNAL_PART_NUMBER") "MCD-00264")
        (field (name "MANUFACTURER") "TEXAS INSTRUMENTS")
        (field (name "PROVIDED_BY") "SUBCO")
      )
      (libsource (lib "MCD_PARTS_database") (part "SN74LVC2T45DCUT"))
    )
    (comp (ref "U24")
      (value "ESDALC6V1W5")
      (footprint "ESD_SOT323-5L")
      (description "Dual Transil array for ESD protection")
      (fields
        (field (name "INTERNAL_PART_NUMBER") "MCD-00136")
        (field (name "MANUFACTURER") "STMICROELECTRONICS")
        (field (name "PROVIDED_BY") "SUBCO with ST control")
      )
      (libsource (lib "MCD_PARTS_database") (part "ESDALC6V1W5"))
    )
    (comp (ref "X1")
      (value "NZ2520SH 25MHz")
      (footprint "OSC_NDK_NZ2520SB_4P")
      (description "Oscillator 25Mhz, +-50ppm, Vcc:3.3V typ, square wave: [0.1Vcc;0.9Vcc], Enable pin, SMD")
      (fields
        (field (name "INTERNAL_PART_NUMBER") "MCD-00597")
        (field (name "MANUFACTURER_PART_NUMBER") "NZ2520SH 25MHz END4869C")
        (field (name "PROVIDED_BY") "SUBCO")
      )
      (libsource (lib "MCD_PARTS_database") (part "OSCILLATOR_4_PINS"))
    )
  )
  (nets
    (net (code "2") (name "/GNDDetect") (class "Default")
      (node (ref "CN5") (pin "11") (pinfunction "11_11") (pintype "passive"))
      (node (ref "R17") (pin "2") (pinfunction "2_2") (pintype "passive"))
      (node (ref "U7") (pin "K13") (pinfunction "GNDDetect/PG5_K13") (pintype "passive"))
    )
    (net (code "3") (name "/LED_STLK") (class "Default")
      (node (ref "R8") (pin "2") (pinfunction "2_2") (pintype "passive"))
      (node (ref "R9") (pin "2") (pinfunction "2_2") (pintype "passive"))
      (node (ref "U7") (pin "D15") (pinfunction "STLK_LED/PA10_D15") (pintype "passive"))
    )
    (net (code "4") (name "/STLK_MCO") (class "Default")
      (node (ref "C5") (pin "2") (pinfunction "2_2") (pintype "passive"))
      (node (ref "R5") (pin "2") (pinfunction "2_2") (pintype "passive"))
    )
    (net (code "5") (name "/STLK_SWCLK") (class "Default")
      (node (ref "CN2") (pin "2") (pinfunction "2_2") (pintype "passive"))
      (node (ref "U3") (pin "1") (pinfunction "IO1_1") (pintype "passive"))
      (node (ref "U7") (pin "A14") (pinfunction "STLK_SWCLK/PA14_A14") (pintype "passive"))
    )
    (net (code "6") (name "/STLK_SWDIO") (class "Default")
      (node (ref "CN2") (pin "4") (pinfunction "4_4") (pintype "passive"))
      (node (ref "U4") (pin "1") (pinfunction "IO1_1") (pintype "passive"))
      (node (ref "U7") (pin "A15") (pinfunction "STLK_SWDIO/PA13_A15") (pintype "passive"))
    )
    (net (code "7") (name "/STLK_VCP_RX") (class "Default")
      (node (ref "SB13") (pin "1") (pinfunction "1_1") (pintype "passive"))
      (node (ref "U1") (pin "3") (pinfunction "A2_3") (pintype "passive"))
      (node (ref "U7") (pin "C10") (pinfunction "STLK_VCP_RX/PG9_C10") (pintype "passive"))
    )
    (net (code "8") (name "/STLK_VCP_TX") (class "Default")
      (node (ref "R23") (pin "1") (pinfunction "1_1") (pintype "passive"))
      (node (ref "U7") (pin "A7") (pinfunction "STLK_VCP_TX/PG14_A7") (pintype "passive"))
    )
    (net (code "9") (name "/T_JTDI") (class "Default")
      (node (ref "CN5") (pin "10") (pinfunction "10_10") (pintype "passive"))
      (node (ref "U8") (pin "1") (pinfunction "IO1_1") (pintype "passive"))
    )
    (net (code "10") (name "/T_NRST") (class "Default")
      (node (ref "CN5") (pin "12") (pinfunction "12_12") (pintype "passive"))
      (node (ref "JP3") (pin "2") (pinfunction "NO_2") (pintype "passive"))
      (node (ref "U24") (pin "5") (pinfunction "IO4_5") (pintype "passive"))
    )
    (net (code "11") (name "/T_NRSTa") (class "Default")
      (node (ref "R29") (pin "1") (pinfunction "1_1") (pintype "passive"))
      (node (ref "U7") (pin "P3") (pinfunction "T_NRST/PA6_P3") (pintype "passive"))
    )
    (net (code "12") (name "/T_PWR_EN") (class "Default")
      (node (ref "R7") (pin "1") (pinfunction "1_1") (pintype "passive"))
      (node (ref "U2") (pin "4") (pinfunction "EN_4") (pintype "passive"))
      (node (ref "U7") (pin "R5") (pinfunction "T_PWR_EN/PB0_R5") (pintype "passive"))
    )
    (net (code "13") (name "/T_PWR_EXT") (class "Default")
      (node (ref "R14") (pin "2") (pinfunction "2_2") (pintype "passive"))
      (node (ref "R15") (pin "2") (pinfunction "2_2") (pintype "passive"))
      (node (ref "U7") (pin "R4") (pinfunction "T_PWR_EXT/PB1_R4") (pintype "passive"))
    )
    (net (code "14") (name "/T_SWCLK") (class "Default")
      (node (ref "CN5") (pin "6") (pinfunction "6_6") (pintype "passive"))
      (node (ref "R11") (pin "2") (pinfunction "2_2") (pintype "passive"))
      (node (ref "U8") (pin "4") (pinfunction "IO3_4") (pintype "passive"))
    )
    (net (code "15") (name "/T_SWCLKa") (class "Default")
      (node (ref "R11") (pin "1") (pinfunction "1_1") (pintype "passive"))
      (node (ref "U7") (pin "M11") (pinfunction "T_SWCLK/PH6_M11") (pintype "passive"))
    )
    (net (code "16") (name "/T_SWDIO") (class "Default")
      (node (ref "CN5") (pin "4") (pinfunction "4_4") (pintype "passive"))
      (node (ref "R10") (pin "1") (pinfunction "1_1") (pintype "passive"))
      (node (ref "U8") (pin "5") (pinfunction "IO4_5") (pintype "passive"))
    )
    (net (code "17") (name "/T_SWDIO_IN") (class "Default")
      (node (ref "R70") (pin "2") (pinfunction "2_2") (pintype "passive"))
      (node (ref "U10") (pin "2") (pinfunction "A1_2") (pintype "passive"))
      (node (ref "U7") (pin "N12") (pinfunction "T_SWDIO_IN/PH7_N12") (pintype "passive"))
    )
    (net (code "18") (name "/T_SWDIOa") (class "Default")
      (node (ref "R10") (pin "2") (pinfunction "2_2") (pintype "passive"))
      (node (ref "R70") (pin "1") (pinfunction "1_1") (pintype "passive"))
      (node (ref "U10") (pin "7") (pinfunction "B1_7") (pintype "passive"))
      (node (ref "U7") (pin "L2") (pinfunction "T_SWDIO_OUT/PF9_L2") (pintype "passive"))
    )
    (net (code "19") (name "/T_SWO") (class "Default")
      (node (ref "CN5") (pin "8") (pinfunction "8_8") (pintype "passive"))
      (node (ref "R13") (pin "1") (pinfunction "1_1") (pintype "passive"))
      (node (ref "U8") (pin "3") (pinfunction "IO2_3") (pintype "passive"))
    )
    (net (code "20") (name "/T_SWOa") (class "Default")
      (node (ref "SB5") (pin "1") (pinfunction "1_1") (pintype "passive"))
      (node (ref "U10") (pin "3") (pinfunction "A2_3") (pintype "passive"))
      (node (ref "U7") (pin "D12") (pinfunction "T_SWO/PD2_D12") (pintype "passive"))
    )
    (net (code "21") (name "/T_VCP_RX") (class "Default")
      (node (ref "CN5") (pin "13") (pinfunction "13_13") (pintype "passive"))
      (node (ref "R23") (pin "2") (pinfunction "2_2") (pintype "passive"))
      (node (ref "U24") (pin "1") (pinfunction "IO1_1") (pintype "passive"))
    )
    (net (code "22") (name "/T_VCP_TX") (class "Default")
      (node (ref "CN5") (pin "14") (pinfunction "14_14") (pintype "passive"))
      (node (ref "R3") (pin "1") (pinfunction "1_1") (pintype "passive"))
      (node (ref "U24") (pin "3") (pinfunction "IO2_3") (pintype "passive"))
    )
    (net (code "23") (name "/USB_DEV_HS_CN_N") (class "Default")
      (node (ref "CN1") (pin "2") (pinfunction "DM_2") (pintype "passive"))
      (node (ref "U5") (pin "5") (pinfunction "D-_5") (pintype "passive"))
    )
    (net (code "24") (name "/USB_DEV_HS_CN_P") (class "Default")
      (node (ref "CN1") (pin "3") (pinfunction "DP_3") (pintype "passive"))
      (node (ref "U5") (pin "6") (pinfunction "D+_6") (pintype "passive"))
    )
    (net (code "25") (name "/USB_DEV_HS_N") (class "Default")
      (node (ref "U5") (pin "2") (pinfunction "D-_2") (pintype "passive"))
      (node (ref "U7") (pin "R14") (pinfunction "USB_DEV_HS_N/PB14_R14") (pintype "passive"))
    )
    (net (code "26") (name "/USB_DEV_HS_P") (class "Default")
      (node (ref "U5") (pin "1") (pinfunction "D+_1") (pintype "passive"))
      (node (ref "U7") (pin "R15") (pinfunction "USB_DEV_HS_P/PB15_R15") (pintype "passive"))
    )
    (net (code "27") (name "3V3_STLK") (class "Default")
      (node (ref "C10") (pin "2") (pinfunction "2_2") (pintype "passive"))
      (node (ref "C11") (pin "2") (pinfunction "2_2") (pintype "passive"))
      (node (ref "C14") (pin "2") (pinfunction "2_2") (pintype "passive"))
      (node (ref "C15") (pin "2") (pinfunction "2_2") (pintype "passive"))
      (node (ref "C16") (pin "2") (pinfunction "2_2") (pintype "passive"))
      (node (ref "C17") (pin "2") (pinfunction "2_2") (pintype "passive"))
      (node (ref "C2") (pin "2") (pinfunction "2_2") (pintype "passive"))
      (node (ref "C21") (pin "2") (pinfunction "2_2") (pintype "passive"))
      (node (ref "C22") (pin "2") (pinfunction "2_2") (pintype "passive"))
      (node (ref "C23") (pin "2") (pinfunction "2_2") (pintype "passive"))
      (node (ref "C24") (pin "2") (pinfunction "2_2") (pintype "passive"))
      (node (ref "C25") (pin "2") (pinfunction "2_2") (pintype "passive"))
      (node (ref "C27") (pin "2") (pinfunction "2_2") (pintype "passive"))
      (node (ref "C29") (pin "2") (pinfunction "2_2") (pintype "passive"))
      (node (ref "C30") (pin "2") (pinfunction "2_2") (pintype "passive"))
      (node (ref "C31") (pin "2") (pinfunction "2_2") (pintype "passive"))
      (node (ref "C32") (pin "2") (pinfunction "2_2") (pintype "passive"))
      (node (ref "C33") (pin "2") (pinfunction "2_2") (pintype "passive"))
      (node (ref "C34") (pin "2") (pinfunction "2_2") (pintype "passive"))
      (node (ref "C35") (pin "2") (pinfunction "2_2") (pintype "passive"))
      (node (ref "C36") (pin "2") (pinfunction "2_2") (pintype "passive"))
      (node (ref "C37") (pin "2") (pinfunction "2_2") (pintype "passive"))
      (node (ref "C8") (pin "2") (pinfunction "2_2") (pintype "passive"))
      (node (ref "C9") (pin "2") (pinfunction "2_2") (pintype "passive"))
      (node (ref "CN2") (pin "1") (pinfunction "1_1") (pintype "passive"))
      (node (ref "LD4") (pin "4") (pinfunction "YellowGreen_anode_4") (pintype "passive"))
      (node (ref "R24") (pin "1") (pinfunction "1_1") (pintype "passive"))
      (node (ref "U1") (pin "1") (pinfunction "VccA_1") (pintype "power_in"))
      (node (ref "U10") (pin "1") (pinfunction "VccA_1") (pintype "power_in"))
      (node (ref "U7") (pin "C1") (pinfunction "VBAT_C1") (pintype "passive"))
      (node (ref "U7") (pin "C5") (pinfunction "VDD_C5") (pintype "passive"))
      (node (ref "U7") (pin "C6") (pinfunction "PDR_ON_C6") (pintype "passive"))
      (node (ref "U7") (pin "C7") (pinfunction "VDD_C7") (pintype "passive"))
      (node (ref "U7") (pin "C8") (pinfunction "VDD_C8") (pintype "passive"))
      (node (ref "U7") (pin "C9") (pinfunction "VDD_C9") (pintype "passive"))
      (node (ref "U7") (pin "F3") (pinfunction "VDD_F3") (pintype "passive"))
      (node (ref "U7") (pin "G13") (pinfunction "VDD_G13") (pintype "passive"))
      (node (ref "U7") (pin "G3") (pinfunction "VDD_G3") (pintype "passive"))
      (node (ref "U7") (pin "H13") (pinfunction "VDD_H13") (pintype "passive"))
      (node (ref "U7") (pin "J12") (pinfunction "VDD_J12") (pintype "passive"))
      (node (ref "U7") (pin "J13") (pinfunction "VDD_J13") (pintype "passive"))
      (node (ref "U7") (pin "K4") (pinfunction "VDD_K4") (pintype "passive"))
      (node (ref "U7") (pin "N10") (pinfunction "VDD_N10") (pintype "passive"))
      (node (ref "U7") (pin "N8") (pinfunction "VDD_N8") (pintype "passive"))
      (node (ref "U7") (pin "N9") (pinfunction "VDD_N9") (pintype "passive"))
      (node (ref "U7") (pin "P1") (pinfunction "VREF+_P1") (pintype "passive"))
      (node (ref "U7") (pin "R1") (pinfunction "VDDA_R1") (pintype "passive"))
      (node (ref "U9") (pin "5") (pinfunction "Vout_5") (pintype "passive"))
      (node (ref "X1") (pin "4") (pinfunction "VDD_4") (pintype "passive"))
    )
    (net (code "28") (name "5V") (class "Default")
      (node (ref "R15") (pin "1") (pinfunction "1_1") (pintype "passive"))
    )
    (net (code "29") (name "5V_EXT") (class "Default")
      (node (ref "D2") (pin "1") (pinfunction "A_1") (pintype "passive"))
    )
    (net (code "30") (name "5V_USB_CHGR") (class "Default")
      (node (ref "C3") (pin "2") (pinfunction "2_2") (pintype "passive"))
      (node (ref "C6") (pin "2") (pinfunction "2_2") (pintype "passive"))
      (node (ref "CN1") (pin "1") (pinfunction "VBUS_1") (pintype "passive"))
      (node (ref "D3") (pin "1") (pinfunction "A_1") (pintype "passive"))
      (node (ref "R1") (pin "2") (pinfunction "2_2") (pintype "passive"))
      (node (ref "R2") (pin "2") (pinfunction "2_2") (pintype "passive"))
      (node (ref "U2") (pin "5") (pinfunction "IN_5") (pintype "passive"))
      (node (ref "U6") (pin "1") (pinfunction "IO1_1") (pintype "passive"))
    )
    (net (code "31") (name "5V_USB_STLK") (class "Default")
      (node (ref "C1") (pin "2") (pinfunction "2_2") (pintype "passive"))
      (node (ref "U2") (pin "1") (pinfunction "OUT_1") (pintype "passive"))
    )
    (net (code "32") (name "5V_VIN") (class "Default")
      (node (ref "D1") (pin "1") (pinfunction "A_1") (pintype "passive"))
    )
    (net (code "33") (name "GND") (class "Default")
      (node (ref "C1") (pin "1") (pinfunction "1_1") (pintype "passive"))
      (node (ref "C10") (pin "1") (pinfunction "1_1") (pintype "passive"))
      (node (ref "C11") (pin "1") (pinfunction "1_1") (pintype "passive"))
      (node (ref "C12") (pin "1") (pinfunction "1_1") (pintype "passive"))
      (node (ref "C13") (pin "1") (pinfunction "1_1") (pintype "passive"))
      (node (ref "C14") (pin "1") (pinfunction "1_1") (pintype "passive"))
      (node (ref "C15") (pin "1") (pinfunction "1_1") (pintype "passive"))
      (node (ref "C16") (pin "1") (pinfunction "1_1") (pintype "passive"))
      (node (ref "C17") (pin "1") (pinfunction "1_1") (pintype "passive"))
      (node (ref "C18") (pin "2") (pinfunction "2_2") (pintype "passive"))
      (node (ref "C19") (pin "1") (pinfunction "1_1") (pintype "passive"))
      (node (ref "C2") (pin "1") (pinfunction "1_1") (pintype "passive"))
      (node (ref "C20") (pin "1") (pinfunction "1_1") (pintype "passive"))
      (node (ref "C21") (pin "1") (pinfunction "1_1") (pintype "passive"))
      (node (ref "C22") (pin "1") (pinfunction "1_1") (pintype "passive"))
      (node (ref "C23") (pin "1") (pinfunction "1_1") (pintype "passive"))
      (node (ref "C24") (pin "1") (pinfunction "1_1") (pintype "passive"))
      (node (ref "C25") (pin "1") (pinfunction "1_1") (pintype "passive"))
      (node (ref "C26") (pin "2") (pinfunction "2_2") (pintype "passive"))
      (node (ref "C27") (pin "1") (pinfunction "1_1") (pintype "passive"))
      (node (ref "C28") (pin "1") (pinfunction "1_1") (pintype "passive"))
      (node (ref "C29") (pin "1") (pinfunction "1_1") (pintype "passive"))
      (node (ref "C3") (pin "1") (pinfunction "1_1") (pintype "passive"))
      (node (ref "C30") (pin "1") (pinfunction "1_1") (pintype "passive"))
      (node (ref "C31") (pin "1") (pinfunction "1_1") (pintype "passive"))
      (node (ref "C32") (pin "1") (pinfunction "1_1") (pintype "passive"))
      (node (ref "C33") (pin "1") (pinfunction "1_1") (pintype "passive"))
      (node (ref "C34") (pin "1") (pinfunction "1_1") (pintype "passive"))
      (node (ref "C35") (pin "1") (pinfunction "1_1") (pintype "passive"))
      (node (ref "C36") (pin "1") (pinfunction "1_1") (pintype "passive"))
      (node (ref "C37") (pin "1") (pinfunction "1_1") (pintype "passive"))
      (node (ref "C4") (pin "2") (pinfunction "2_2") (pintype "passive"))
      (node (ref "C5") (pin "1") (pinfunction "1_1") (pintype "passive"))
      (node (ref "C6") (pin "1") (pinfunction "1_1") (pintype "passive"))
      (node (ref "C7") (pin "1") (pinfunction "1_1") (pintype "passive"))
      (node (ref "C8") (pin "1") (pinfunction "1_1") (pintype "passive"))
      (node (ref "C9") (pin "1") (pinfunction "1_1") (pintype "passive"))
      (node (ref "CN1") (pin "10") (pinfunction "EXP_10") (pintype "passive"))
      (node (ref "CN1") (pin "11") (pinfunction "EXP_11") (pintype "passive"))
      (node (ref "CN1") (pin "5") (pinfunction "GND_5") (pintype "passive"))
      (node (ref "CN1") (pin "6") (pinfunction "Shield_6") (pintype "passive"))
      (node (ref "CN1") (pin "7") (pinfunction "Shield_7") (pintype "passive"))
      (node (ref "CN1") (pin "8") (pinfunction "Shield_8") (pintype "passive"))
      (node (ref "CN1") (pin "9") (pinfunction "Shield_9") (pintype "passive"))
      (node (ref "CN2") (pin "3") (pinfunction "3_3") (pintype "passive"))
      (node (ref "CN3") (pin "1") (pinfunction "COMMON_1") (pintype "passive"))
      (node (ref "CN3") (pin "2") (pinfunction "NO_2") (pintype "passive"))
      (node (ref "CN4") (pin "1") (pinfunction "COMMON_1") (pintype "passive"))
      (node (ref "CN4") (pin "2") (pinfunction "NO_2") (pintype "passive"))
      (node (ref "CN5") (pin "5") (pinfunction "5_5") (pintype "passive"))
      (node (ref "CN5") (pin "7") (pinfunction "7_7") (pintype "passive"))
      (node (ref "JP1") (pin "1") (pinfunction "COMMON_1") (pintype "passive"))
      (node (ref "LD4") (pin "1") (pinfunction "RED_cathode_1") (pintype "passive"))
      (node (ref "R14") (pin "1") (pinfunction "1_1") (pintype "passive"))
      (node (ref "R17") (pin "1") (pinfunction "1_1") (pintype "passive"))
      (node (ref "R18") (pin "2") (pinfunction "2_2") (pintype "passive"))
      (node (ref "R22") (pin "1") (pinfunction "1_1") (pintype "passive"))
      (node (ref "R6") (pin "1") (pinfunction "1_1") (pintype "passive"))
      (node (ref "R7") (pin "2") (pinfunction "2_2") (pintype "passive"))
      (node (ref "U1") (pin "4") (pinfunction "GND_4") (pintype "power_in"))
      (node (ref "U1") (pin "5") (pinfunction "DIR_5") (pintype "passive"))
      (node (ref "U10") (pin "4") (pinfunction "GND_4") (pintype "power_in"))
      (node (ref "U10") (pin "5") (pinfunction "DIR_5") (pintype "passive"))
      (node (ref "U2") (pin "2") (pinfunction "GND_2") (pintype "passive"))
      (node (ref "U24") (pin "2") (pinfunction "GND_2") (pintype "passive"))
      (node (ref "U3") (pin "2") (pinfunction "GND_2") (pintype "passive"))
      (node (ref "U4") (pin "2") (pinfunction "GND_2") (pintype "passive"))
      (node (ref "U5") (pin "3") (pinfunction "GND_3") (pintype "passive"))
      (node (ref "U6") (pin "2") (pinfunction "GND_2") (pintype "passive"))
      (node (ref "U7") (pin "D5") (pinfunction "VSS_D5") (pintype "passive"))
      (node (ref "U7") (pin "D6") (pinfunction "BOOT0_D6") (pintype "passive"))
      (node (ref "U7") (pin "D7") (pinfunction "VSS_D7") (pintype "passive"))
      (node (ref "U7") (pin "D8") (pinfunction "VSS_D8") (pintype "passive"))
      (node (ref "U7") (pin "D9") (pinfunction "VSS_D9") (pintype "passive"))
      (node (ref "U7") (pin "F10") (pinfunction "VSS_F10") (pintype "passive"))
      (node (ref "U7") (pin "F12") (pinfunction "VSS_F12") (pintype "passive"))
      (node (ref "U7") (pin "F2") (pinfunction "VSS_F2") (pintype "passive"))
      (node (ref "U7") (pin "F6") (pinfunction "VSS_F6") (pintype "passive"))
      (node (ref "U7") (pin "F7") (pinfunction "VSS_F7") (pintype "passive"))
      (node (ref "U7") (pin "F8") (pinfunction "VSS_F8") (pintype "passive"))
      (node (ref "U7") (pin "F9") (pinfunction "VSS_F9") (pintype "passive"))
      (node (ref "U7") (pin "G10") (pinfunction "VSS_G10") (pintype "passive"))
      (node (ref "U7") (pin "G12") (pinfunction "VSS_G12") (pintype "passive"))
      (node (ref "U7") (pin "G2") (pinfunction "VSS_G2") (pintype "passive"))
      (node (ref "U7") (pin "G6") (pinfunction "VSS_G6") (pintype "passive"))
      (node (ref "U7") (pin "G7") (pinfunction "VSS_G7") (pintype "passive"))
      (node (ref "U7") (pin "G8") (pinfunction "VSS_G8") (pintype "passive"))
      (node (ref "U7") (pin "G9") (pinfunction "VSS_G9") (pintype "passive"))
      (node (ref "U7") (pin "H10") (pinfunction "VSS_H10") (pintype "passive"))
      (node (ref "U7") (pin "H12") (pinfunction "VSS_H12") (pintype "passive"))
      (node (ref "U7") (pin "H6") (pinfunction "VSS_H6") (pintype "passive"))
      (node (ref "U7") (pin "H7") (pinfunction "VSS_H7") (pintype "passive"))
      (node (ref "U7") (pin "H8") (pinfunction "VSS_H8") (pintype "passive"))
      (node (ref "U7") (pin "H9") (pinfunction "VSS_H9") (pintype "passive"))
      (node (ref "U7") (pin "J10") (pinfunction "VSS_J10") (pintype "passive"))
      (node (ref "U7") (pin "J6") (pinfunction "VSS_J6") (pintype "passive"))
      (node (ref "U7") (pin "J7") (pinfunction "VSS_J7") (pintype "passive"))
      (node (ref "U7") (pin "J8") (pinfunction "VSS_J8") (pintype "passive"))
      (node (ref "U7") (pin "J9") (pinfunction "VSS_J9") (pintype "passive"))
      (node (ref "U7") (pin "K10") (pinfunction "VSS_K10") (pintype "passive"))
      (node (ref "U7") (pin "K6") (pinfunction "VSS_K6") (pintype "passive"))
      (node (ref "U7") (pin "K7") (pinfunction "VSS_K7") (pintype "passive"))
      (node (ref "U7") (pin "K8") (pinfunction "VSS_K8") (pintype "passive"))
      (node (ref "U7") (pin "K9") (pinfunction "VSS_K9") (pintype "passive"))
      (node (ref "U7") (pin "M1") (pinfunction "VSSA_M1") (pintype "passive"))
      (node (ref "U7") (pin "M8") (pinfunction "VSS_M8") (pintype "passive"))
      (node (ref "U7") (pin "M9") (pinfunction "VSS_M9") (pintype "passive"))
      (node (ref "U7") (pin "N1") (pinfunction "VREF-_N1") (pintype "passive"))
      (node (ref "U8") (pin "2") (pinfunction "GND_2") (pintype "passive"))
      (node (ref "U9") (pin "2") (pinfunction "GND_2") (pintype "passive"))
      (node (ref "X1") (pin "2") (pinfunction "GND_2") (pintype "passive"))
    )
    (net (code "34") (name "Net-(D1-K)") (class "Default")
      (node (ref "C18") (pin "1") (pinfunction "1_1") (pintype "passive"))
      (node (ref "C20") (pin "2") (pinfunction "2_2") (pintype "passive"))
      (node (ref "D1") (pin "2") (pinfunction "K_2") (pintype "passive"))
      (node (ref "D2") (pin "2") (pinfunction "K_2") (pintype "passive"))
      (node (ref "D3") (pin "2") (pinfunction "K_2") (pintype "passive"))
      (node (ref "U9") (pin "1") (pinfunction "Vin_1") (pintype "passive"))
      (node (ref "U9") (pin "3") (pinfunction "CE_3") (pintype "passive"))
    )
    (net (code "35") (name "Net-(JP1-NO)") (class "Default")
      (node (ref "C28") (pin "2") (pinfunction "2_2") (pintype "passive"))
      (node (ref "JP1") (pin "2") (pinfunction "NO_2") (pintype "passive"))
      (node (ref "U7") (pin "J1") (pinfunction "NRST_J1") (pintype "passive"))
    )
    (net (code "36") (name "Net-(JP3-COMMON)") (class "Default")
      (node (ref "JP3") (pin "1") (pinfunction "COMMON_1") (pintype "passive"))
      (node (ref "R29") (pin "2") (pinfunction "2_2") (pintype "passive"))
    )
    (net (code "37") (name "Net-(LD4-Red_anode)") (class "Default")
      (node (ref "LD4") (pin "2") (pinfunction "Red_anode_2") (pintype "passive"))
      (node (ref "R9") (pin "1") (pinfunction "1_1") (pintype "passive"))
    )
    (net (code "38") (name "Net-(LD4-YellowGreen_cathode)") (class "Default")
      (node (ref "LD4") (pin "3") (pinfunction "YellowGreen_cathode_3") (pintype "passive"))
      (node (ref "R8") (pin "1") (pinfunction "1_1") (pintype "passive"))
    )
    (net (code "39") (name "Net-(LD6-Pad1)") (class "Default")
      (node (ref "LD6") (pin "1") (pintype "passive"))
      (node (ref "R2") (pin "1") (pinfunction "1_1") (pintype "passive"))
    )
    (net (code "40") (name "Net-(U1-B1)") (class "Default")
      (node (ref "R4") (pin "1") (pinfunction "1_1") (pintype "passive"))
      (node (ref "U1") (pin "7") (pinfunction "B1_7") (pintype "passive"))
    )
    (net (code "41") (name "Net-(U1-B2)") (class "Default")
      (node (ref "R3") (pin "2") (pinfunction "2_2") (pintype "passive"))
      (node (ref "SB13") (pin "2") (pinfunction "2_2") (pintype "passive"))
      (node (ref "U1") (pin "6") (pinfunction "B2_6") (pintype "passive"))
    )
    (net (code "42") (name "Net-(U2-~{FAULT})") (class "Default")
      (node (ref "LD6") (pin "2") (pintype "passive"))
      (node (ref "R1") (pin "1") (pinfunction "1_1") (pintype "passive"))
      (node (ref "U2") (pin "3") (pinfunction "~{FAULT}_3") (pintype "passive"))
    )
    (net (code "43") (name "Net-(U7A-OSC_IN{slash}PH0)") (class "Default")
      (node (ref "R21") (pin "2") (pinfunction "2_2") (pintype "passive"))
      (node (ref "U7") (pin "G1") (pinfunction "OSC_IN/PH0_G1") (pintype "passive"))
    )
    (net (code "44") (name "Net-(U7A-REXT_OTGPHY)") (class "Default")
      (node (ref "R6") (pin "2") (pinfunction "2_2") (pintype "passive"))
      (node (ref "U7") (pin "J15") (pinfunction "REXT_OTGPHY_J15") (pintype "passive"))
    )
    (net (code "45") (name "Net-(U7A-STLK_MCO{slash}PA8)") (class "Default")
      (node (ref "R5") (pin "1") (pinfunction "1_1") (pintype "passive"))
      (node (ref "U7") (pin "F15") (pinfunction "STLK_MCO/PA8_F15") (pintype "passive"))
    )
    (net (code "46") (name "Net-(U7A-T_VCC_AIN{slash}PA0)") (class "Default")
      (node (ref "R18") (pin "1") (pinfunction "1_1") (pintype "passive"))
      (node (ref "R20") (pin "1") (pinfunction "1_1") (pintype "passive"))
      (node (ref "U7") (pin "N3") (pinfunction "T_VCC_AIN/PA0_N3") (pintype "passive"))
    )
    (net (code "47") (name "Net-(U7A-V12_OTGPHY)") (class "Default")
      (node (ref "C7") (pin "2") (pinfunction "2_2") (pintype "passive"))
      (node (ref "U7") (pin "J14") (pinfunction "V12_OTGPHY_J14") (pintype "passive"))
    )
    (net (code "48") (name "Net-(U7B-BYPASS-REG)") (class "Default")
      (node (ref "R22") (pin "2") (pinfunction "2_2") (pintype "passive"))
      (node (ref "U7") (pin "L4") (pinfunction "BYPASS-REG_L4") (pintype "passive"))
    )
    (net (code "49") (name "Net-(U7B-VCAP1)") (class "Default")
      (node (ref "C13") (pin "2") (pinfunction "2_2") (pintype "passive"))
      (node (ref "U7") (pin "M10") (pinfunction "VCAP1_M10") (pintype "passive"))
    )
    (net (code "50") (name "Net-(U7B-VCAP2)") (class "Default")
      (node (ref "C12") (pin "2") (pinfunction "2_2") (pintype "passive"))
      (node (ref "U7") (pin "F13") (pinfunction "VCAP2_F13") (pintype "passive"))
    )
    (net (code "51") (name "Net-(U9-BYPASS)") (class "Default")
      (node (ref "C19") (pin "2") (pinfunction "2_2") (pintype "passive"))
      (node (ref "U9") (pin "4") (pinfunction "BYPASS_4") (pintype "passive"))
    )
    (net (code "52") (name "Net-(U10-B2)") (class "Default")
      (node (ref "R13") (pin "2") (pinfunction "2_2") (pintype "passive"))
      (node (ref "SB5") (pin "2") (pinfunction "2_2") (pintype "passive"))
      (node (ref "U10") (pin "6") (pinfunction "B2_6") (pintype "passive"))
    )
    (net (code "53") (name "Net-(X1-EN)") (class "Default")
      (node (ref "R24") (pin "2") (pinfunction "2_2") (pintype "passive"))
      (node (ref "X1") (pin "1") (pinfunction "EN_1") (pintype "passive"))
    )
    (net (code "54") (name "Net-(X1-OUT)") (class "Default")
      (node (ref "R21") (pin "1") (pinfunction "1_1") (pintype "passive"))
      (node (ref "X1") (pin "3") (pinfunction "OUT_3") (pintype "passive"))
    )
    (net (code "55") (name "VDD") (class "Default")
      (node (ref "C26") (pin "1") (pinfunction "1_1") (pintype "passive"))
      (node (ref "C4") (pin "1") (pinfunction "1_1") (pintype "passive"))
      (node (ref "CN5") (pin "3") (pinfunction "3_3") (pintype "passive"))
      (node (ref "R20") (pin "2") (pinfunction "2_2") (pintype "passive"))
      (node (ref "R4") (pin "2") (pinfunction "2_2") (pintype "passive"))
      (node (ref "U1") (pin "8") (pinfunction "VccB_8") (pintype "power_in"))
      (node (ref "U10") (pin "8") (pinfunction "VccB_8") (pintype "power_in"))
    )
    (net (code "56") (name "unconnected-(CN1-ID-Pad4)") (class "Default")
      (node (ref "CN1") (pin "4") (pinfunction "ID_4") (pintype "passive+no_connect"))
    )
    (net (code "57") (name "unconnected-(CN5-Pad1)") (class "Default")
      (node (ref "CN5") (pin "1") (pinfunction "1_1") (pintype "passive+no_connect"))
    )
    (net (code "58") (name "unconnected-(CN5-Pad2)") (class "Default")
      (node (ref "CN5") (pin "2") (pinfunction "2_2") (pintype "passive+no_connect"))
    )
    (net (code "59") (name "unconnected-(CN5-Pad9)") (class "Default")
      (node (ref "CN5") (pin "9") (pinfunction "9_9") (pintype "passive+no_connect"))
    )
    (net (code "60") (name "unconnected-(U1-A1-Pad2)") (class "Default")
      (node (ref "U1") (pin "2") (pinfunction "A1_2") (pintype "passive+no_connect"))
    )
    (net (code "61") (name "unconnected-(U5-NC-Pad4)") (class "Default")
      (node (ref "U5") (pin "4") (pinfunction "NC_4") (pintype "passive+no_connect"))
    )
    (net (code "62") (name "unconnected-(U7A-HW_TYP_0{slash}PI4-PadD4)") (class "Default")
      (node (ref "U7") (pin "D4") (pinfunction "HW_TYP_0/PI4_D4") (pintype "passive+no_connect"))
    )
    (net (code "63") (name "unconnected-(U7A-HW_TYP_1{slash}PI5-PadC4)") (class "Default")
      (node (ref "U7") (pin "C4") (pinfunction "HW_TYP_1/PI5_C4") (pintype "passive+no_connect"))
    )
    (net (code "64") (name "unconnected-(U7A-OSC_OUT{slash}PH1-PadH1)") (class "Default")
      (node (ref "U7") (pin "H1") (pinfunction "OSC_OUT/PH1_H1") (pintype "passive+no_connect"))
    )
    (net (code "65") (name "unconnected-(U7A-T_SW_DIR{slash}PA7-PadR3)") (class "Default")
      (node (ref "U7") (pin "R3") (pinfunction "T_SW_DIR/PA7_R3") (pintype "passive+no_connect"))
    )
    (net (code "66") (name "unconnected-(U24-IO3-Pad4)") (class "Default")
      (node (ref "U24") (pin "4") (pinfunction "IO3_4") (pintype "passive+no_connect"))
    )
  )
)
